# 7-Segment_display.net
KiCad netlist of a schematic drawn in EAGLE
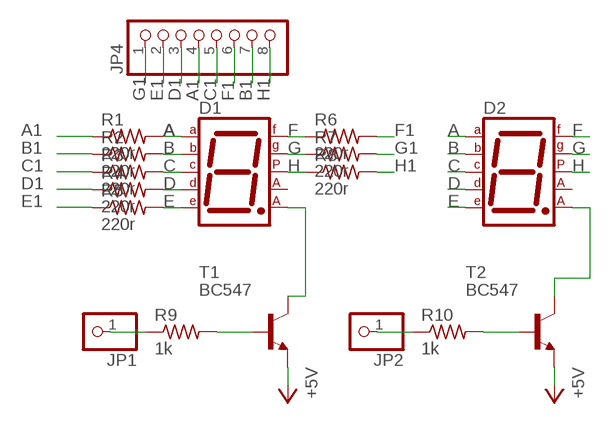
[diagram p0: schematic, sheet 1]

(export (version "E")
  (design (tool "Eeschema 10.0.6"))
  (components
    (comp (ref "D1")
      (value "7SEG-CA")
      (footprint "eagle-import:7SEG-13")
      (libsource (lib "eagle-import") (part "7SEG-CA"))
    )
    (comp (ref "D2")
      (value "7SEG-CA")
      (footprint "eagle-import:7SEG-13")
      (libsource (lib "eagle-import") (part "7SEG-CA"))
    )
    (comp (ref "JP1")
      (value "PINHD-1X1")
      (footprint "eagle-import:1X01")
      (libsource (lib "eagle-import") (part "PINHD-1X1"))
    )
    (comp (ref "JP2")
      (value "PINHD-1X1")
      (footprint "eagle-import:1X01")
      (libsource (lib "eagle-import") (part "PINHD-1X1"))
    )
    (comp (ref "JP4")
      (value "PINHD-1X8")
      (footprint "eagle-import:1X08")
      (libsource (lib "eagle-import") (part "PINHD-1X8"))
    )
    (comp (ref "R1")
      (value "220r")
      (footprint "eagle-import:0207_10")
      (libsource (lib "eagle-import") (part "R-US_0207/10"))
    )
    (comp (ref "R2")
      (value "220r")
      (footprint "eagle-import:0207_10")
      (libsource (lib "eagle-import") (part "R-US_0207/10"))
    )
    (comp (ref "R3")
      (value "220r")
      (footprint "eagle-import:0207_10")
      (libsource (lib "eagle-import") (part "R-US_0207/10"))
    )
    (comp (ref "R4")
      (value "220r")
      (footprint "eagle-import:0207_10")
      (libsource (lib "eagle-import") (part "R-US_0207/10"))
    )
    (comp (ref "R5")
      (value "220r")
      (footprint "eagle-import:0207_10")
      (libsource (lib "eagle-import") (part "R-US_0207/10"))
    )
    (comp (ref "R6")
      (value "220r")
      (footprint "eagle-import:0207_10")
      (libsource (lib "eagle-import") (part "R-US_0207/10"))
    )
    (comp (ref "R7")
      (value "220r")
      (footprint "eagle-import:0207_10")
      (libsource (lib "eagle-import") (part "R-US_0207/10"))
    )
    (comp (ref "R8")
      (value "220r")
      (footprint "eagle-import:0207_10")
      (libsource (lib "eagle-import") (part "R-US_0207/10"))
    )
    (comp (ref "R9")
      (value "1k")
      (footprint "eagle-import:0207_10")
      (libsource (lib "eagle-import") (part "R-US_0207/10"))
    )
    (comp (ref "R10")
      (value "1k")
      (footprint "eagle-import:0207_10")
      (libsource (lib "eagle-import") (part "R-US_0207/10"))
    )
    (comp (ref "T1")
      (value "BC547")
      (footprint "eagle-import:TO92")
      (libsource (lib "eagle-import") (part "BC547"))
    )
    (comp (ref "T2")
      (value "BC547")
      (footprint "eagle-import:TO92")
      (libsource (lib "eagle-import") (part "BC547"))
    )
  )
  (nets
    (net (code "1") (name "+5V") (class "Default")
      (node (ref "T1") (pin "1") (pinfunction "E_1") (pintype "passive"))
      (node (ref "T2") (pin "1") (pinfunction "E_1") (pintype "passive"))
    )
    (net (code "2") (name "/A") (class "Default")
      (node (ref "D1") (pin "7") (pinfunction "A_7") (pintype "passive"))
      (node (ref "D2") (pin "7") (pinfunction "A_7") (pintype "passive"))
      (node (ref "R1") (pin "2") (pinfunction "2_2") (pintype "passive"))
    )
    (net (code "3") (name "/A1") (class "Default")
      (node (ref "JP4") (pin "4") (pinfunction "4_4") (pintype "passive"))
      (node (ref "R1") (pin "1") (pinfunction "1_1") (pintype "passive"))
    )
    (net (code "4") (name "/B") (class "Default")
      (node (ref "D1") (pin "6") (pinfunction "B_6") (pintype "passive"))
      (node (ref "D2") (pin "6") (pinfunction "B_6") (pintype "passive"))
      (node (ref "R2") (pin "2") (pinfunction "2_2") (pintype "passive"))
    )
    (net (code "5") (name "/B1") (class "Default")
      (node (ref "JP4") (pin "7") (pinfunction "7_7") (pintype "passive"))
      (node (ref "R2") (pin "1") (pinfunction "1_1") (pintype "passive"))
    )
    (net (code "6") (name "/C") (class "Default")
      (node (ref "D1") (pin "4") (pinfunction "C_4") (pintype "passive"))
      (node (ref "D2") (pin "4") (pinfunction "C_4") (pintype "passive"))
      (node (ref "R3") (pin "2") (pinfunction "2_2") (pintype "passive"))
    )
    (net (code "7") (name "/C1") (class "Default")
      (node (ref "JP4") (pin "5") (pinfunction "5_5") (pintype "passive"))
      (node (ref "R3") (pin "1") (pinfunction "1_1") (pintype "passive"))
    )
    (net (code "8") (name "/D") (class "Default")
      (node (ref "D1") (pin "2") (pinfunction "D_2") (pintype "passive"))
      (node (ref "D2") (pin "2") (pinfunction "D_2") (pintype "passive"))
      (node (ref "R4") (pin "2") (pinfunction "2_2") (pintype "passive"))
    )
    (net (code "9") (name "/D1") (class "Default")
      (node (ref "JP4") (pin "3") (pinfunction "3_3") (pintype "passive"))
      (node (ref "R4") (pin "1") (pinfunction "1_1") (pintype "passive"))
    )
    (net (code "10") (name "/E") (class "Default")
      (node (ref "D1") (pin "1") (pinfunction "E_1") (pintype "passive"))
      (node (ref "D2") (pin "1") (pinfunction "E_1") (pintype "passive"))
      (node (ref "R5") (pin "2") (pinfunction "2_2") (pintype "passive"))
    )
    (net (code "11") (name "/E1") (class "Default")
      (node (ref "JP4") (pin "2") (pinfunction "2_2") (pintype "passive"))
      (node (ref "R5") (pin "1") (pinfunction "1_1") (pintype "passive"))
    )
    (net (code "12") (name "/F") (class "Default")
      (node (ref "D1") (pin "9") (pinfunction "F_9") (pintype "passive"))
      (node (ref "D2") (pin "9") (pinfunction "F_9") (pintype "passive"))
      (node (ref "R6") (pin "1") (pinfunction "1_1") (pintype "passive"))
    )
    (net (code "13") (name "/F1") (class "Default")
      (node (ref "JP4") (pin "6") (pinfunction "6_6") (pintype "passive"))
      (node (ref "R6") (pin "2") (pinfunction "2_2") (pintype "passive"))
    )
    (net (code "14") (name "/G") (class "Default")
      (node (ref "D1") (pin "10") (pinfunction "G_10") (pintype "passive"))
      (node (ref "D2") (pin "10") (pinfunction "G_10") (pintype "passive"))
      (node (ref "R7") (pin "1") (pinfunction "1_1") (pintype "passive"))
    )
    (net (code "15") (name "/G1") (class "Default")
      (node (ref "JP4") (pin "1") (pinfunction "1_1") (pintype "passive"))
      (node (ref "R7") (pin "2") (pinfunction "2_2") (pintype "passive"))
    )
    (net (code "16") (name "/H") (class "Default")
      (node (ref "D1") (pin "5") (pinfunction "DP_5") (pintype "passive"))
      (node (ref "D2") (pin "5") (pinfunction "DP_5") (pintype "passive"))
      (node (ref "R8") (pin "1") (pinfunction "1_1") (pintype "passive"))
    )
    (net (code "17") (name "/H1") (class "Default")
      (node (ref "JP4") (pin "8") (pinfunction "8_8") (pintype "passive"))
      (node (ref "R8") (pin "2") (pinfunction "2_2") (pintype "passive"))
    )
    (net (code "18") (name "Net-(D1-CA2)") (class "Default")
      (node (ref "D1") (pin "8") (pinfunction "CA2_8") (pintype "passive"))
      (node (ref "T1") (pin "3") (pinfunction "C_3") (pintype "passive"))
    )
    (net (code "19") (name "Net-(D2-CA2)") (class "Default")
      (node (ref "D2") (pin "8") (pinfunction "CA2_8") (pintype "passive"))
      (node (ref "T2") (pin "3") (pinfunction "C_3") (pintype "passive"))
    )
    (net (code "20") (name "Net-(JP1-Pad1)") (class "Default")
      (node (ref "JP1") (pin "1") (pinfunction "1_1") (pintype "passive"))
      (node (ref "R9") (pin "1") (pinfunction "1_1") (pintype "passive"))
    )
    (net (code "21") (name "Net-(JP2-Pad1)") (class "Default")
      (node (ref "JP2") (pin "1") (pinfunction "1_1") (pintype "passive"))
      (node (ref "R10") (pin "1") (pinfunction "1_1") (pintype "passive"))
    )
    (net (code "22") (name "Net-(T1-B)") (class "Default")
      (node (ref "R9") (pin "2") (pinfunction "2_2") (pintype "passive"))
      (node (ref "T1") (pin "2") (pinfunction "B_2") (pintype "passive"))
    )
    (net (code "23") (name "Net-(T2-B)") (class "Default")
      (node (ref "R10") (pin "2") (pinfunction "2_2") (pintype "passive"))
      (node (ref "T2") (pin "2") (pinfunction "B_2") (pintype "passive"))
    )
    (net (code "24") (name "unconnected-(D1-CA1-Pad3)") (class "Default")
      (node (ref "D1") (pin "3") (pinfunction "CA1_3") (pintype "passive"))
    )
    (net (code "25") (name "unconnected-(D2-CA1-Pad3)") (class "Default")
      (node (ref "D2") (pin "3") (pinfunction "CA1_3") (pintype "passive"))
    )
  )
)
